# JN5168_Programmer.net
KiCad netlist of a schematic drawn in EAGLE
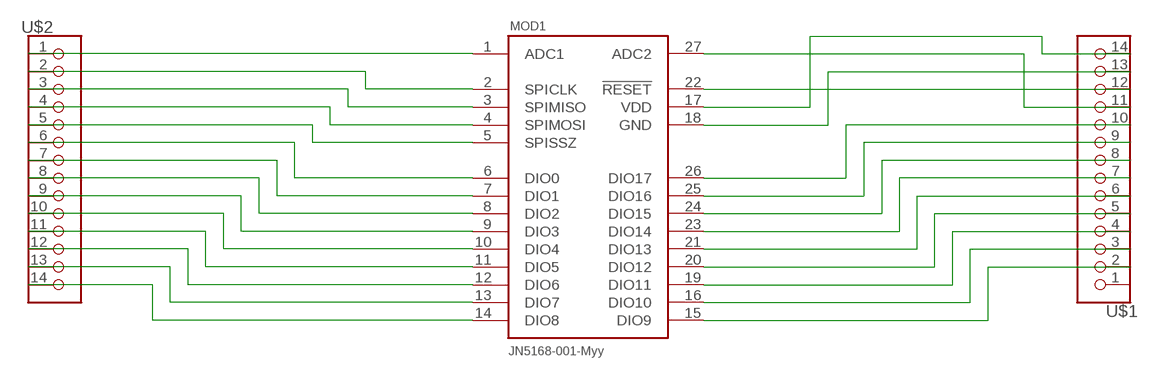
[diagram p0: schematic, sheet 1]

(export (version "E")
  (design (tool "Eeschema 10.0.6"))
  (components
    (comp (ref "MOD1")
      (value "JN5168-001-M00")
      (footprint "eagle-import:JN5168-001-M00")
      (libsource (lib "eagle-import") (part "JN5168-001-M00"))
    )
    (comp (ref "U$1")
      (value "HEADER_1X14_100MIL_PTH")
      (footprint "eagle-import:HEADER_100MIL_1X14_PTH")
      (libsource (lib "eagle-import") (part "HEADER_1X14_100MIL_PTH"))
    )
    (comp (ref "U$2")
      (value "HEADER_1X14_100MIL_PTH")
      (footprint "eagle-import:HEADER_100MIL_1X14_PTH")
      (libsource (lib "eagle-import") (part "HEADER_1X14_100MIL_PTH"))
    )
  )
  (nets
    (net (code "1") (name "Net-(MOD1-ADC1)") (class "Default")
      (node (ref "MOD1") (pin "1") (pinfunction "ADC1_1") (pintype "bidirectional"))
      (node (ref "U$2") (pin "1") (pinfunction "1_1") (pintype "passive"))
    )
    (net (code "2") (name "Net-(MOD1-ADC2)") (class "Default")
      (node (ref "MOD1") (pin "27") (pinfunction "ADC2_27") (pintype "bidirectional"))
      (node (ref "U$1") (pin "11") (pinfunction "11_11") (pintype "passive"))
    )
    (net (code "3") (name "Net-(MOD1-DIO0)") (class "Default")
      (node (ref "MOD1") (pin "6") (pinfunction "DIO0_6") (pintype "bidirectional"))
      (node (ref "U$2") (pin "6") (pinfunction "6_6") (pintype "passive"))
    )
    (net (code "4") (name "Net-(MOD1-DIO1)") (class "Default")
      (node (ref "MOD1") (pin "7") (pinfunction "DIO1_7") (pintype "bidirectional"))
      (node (ref "U$2") (pin "7") (pinfunction "7_7") (pintype "passive"))
    )
    (net (code "5") (name "Net-(MOD1-DIO2)") (class "Default")
      (node (ref "MOD1") (pin "8") (pinfunction "DIO2_8") (pintype "bidirectional"))
      (node (ref "U$2") (pin "8") (pinfunction "8_8") (pintype "passive"))
    )
    (net (code "6") (name "Net-(MOD1-DIO3)") (class "Default")
      (node (ref "MOD1") (pin "9") (pinfunction "DIO3_9") (pintype "bidirectional"))
      (node (ref "U$2") (pin "9") (pinfunction "9_9") (pintype "passive"))
    )
    (net (code "7") (name "Net-(MOD1-DIO4)") (class "Default")
      (node (ref "MOD1") (pin "10") (pinfunction "DIO4_10") (pintype "bidirectional"))
      (node (ref "U$2") (pin "10") (pinfunction "10_10") (pintype "passive"))
    )
    (net (code "8") (name "Net-(MOD1-DIO5)") (class "Default")
      (node (ref "MOD1") (pin "11") (pinfunction "DIO5_11") (pintype "bidirectional"))
      (node (ref "U$2") (pin "11") (pinfunction "11_11") (pintype "passive"))
    )
    (net (code "9") (name "Net-(MOD1-DIO6)") (class "Default")
      (node (ref "MOD1") (pin "12") (pinfunction "DIO6_12") (pintype "bidirectional"))
      (node (ref "U$2") (pin "12") (pinfunction "12_12") (pintype "passive"))
    )
    (net (code "10") (name "Net-(MOD1-DIO7)") (class "Default")
      (node (ref "MOD1") (pin "13") (pinfunction "DIO7_13") (pintype "bidirectional"))
      (node (ref "U$2") (pin "13") (pinfunction "13_13") (pintype "passive"))
    )
    (net (code "11") (name "Net-(MOD1-DIO8)") (class "Default")
      (node (ref "MOD1") (pin "14") (pinfunction "DIO8_14") (pintype "bidirectional"))
      (node (ref "U$2") (pin "14") (pinfunction "14_14") (pintype "passive"))
    )
    (net (code "12") (name "Net-(MOD1-DIO9)") (class "Default")
      (node (ref "MOD1") (pin "15") (pinfunction "DIO9_15") (pintype "bidirectional"))
      (node (ref "U$1") (pin "2") (pinfunction "2_2") (pintype "passive"))
    )
    (net (code "13") (name "Net-(MOD1-DIO10)") (class "Default")
      (node (ref "MOD1") (pin "16") (pinfunction "DIO10_16") (pintype "bidirectional"))
      (node (ref "U$1") (pin "3") (pinfunction "3_3") (pintype "passive"))
    )
    (net (code "14") (name "Net-(MOD1-DIO11)") (class "Default")
      (node (ref "MOD1") (pin "19") (pinfunction "DIO11_19") (pintype "bidirectional"))
      (node (ref "U$1") (pin "4") (pinfunction "4_4") (pintype "passive"))
    )
    (net (code "15") (name "Net-(MOD1-DIO12)") (class "Default")
      (node (ref "MOD1") (pin "20") (pinfunction "DIO12_20") (pintype "bidirectional"))
      (node (ref "U$1") (pin "5") (pinfunction "5_5") (pintype "passive"))
    )
    (net (code "16") (name "Net-(MOD1-DIO13)") (class "Default")
      (node (ref "MOD1") (pin "21") (pinfunction "DIO13_21") (pintype "bidirectional"))
      (node (ref "U$1") (pin "6") (pinfunction "6_6") (pintype "passive"))
    )
    (net (code "17") (name "Net-(MOD1-DIO14)") (class "Default")
      (node (ref "MOD1") (pin "23") (pinfunction "DIO14_23") (pintype "bidirectional"))
      (node (ref "U$1") (pin "7") (pinfunction "7_7") (pintype "passive"))
    )
    (net (code "18") (name "Net-(MOD1-DIO15)") (class "Default")
      (node (ref "MOD1") (pin "24") (pinfunction "DIO15_24") (pintype "bidirectional"))
      (node (ref "U$1") (pin "8") (pinfunction "8_8") (pintype "passive"))
    )
    (net (code "19") (name "Net-(MOD1-DIO16)") (class "Default")
      (node (ref "MOD1") (pin "25") (pinfunction "DIO16_25") (pintype "bidirectional"))
      (node (ref "U$1") (pin "9") (pinfunction "9_9") (pintype "passive"))
    )
    (net (code "20") (name "Net-(MOD1-DIO17)") (class "Default")
      (node (ref "MOD1") (pin "26") (pinfunction "DIO17_26") (pintype "bidirectional"))
      (node (ref "U$1") (pin "10") (pinfunction "10_10") (pintype "passive"))
    )
    (net (code "21") (name "Net-(MOD1-GND)") (class "Default")
      (node (ref "MOD1") (pin "18") (pinfunction "GND_18") (pintype "power_in"))
      (node (ref "U$1") (pin "13") (pinfunction "13_13") (pintype "passive"))
    )
    (net (code "22") (name "Net-(MOD1-SPICLK)") (class "Default")
      (node (ref "MOD1") (pin "2") (pinfunction "SPICLK_2") (pintype "bidirectional"))
      (node (ref "U$2") (pin "2") (pinfunction "2_2") (pintype "passive"))
    )
    (net (code "23") (name "Net-(MOD1-SPIMISO)") (class "Default")
      (node (ref "MOD1") (pin "3") (pinfunction "SPIMISO_3") (pintype "bidirectional"))
      (node (ref "U$2") (pin "3") (pinfunction "3_3") (pintype "passive"))
    )
    (net (code "24") (name "Net-(MOD1-SPIMOSI)") (class "Default")
      (node (ref "MOD1") (pin "4") (pinfunction "SPIMOSI_4") (pintype "bidirectional"))
      (node (ref "U$2") (pin "4") (pinfunction "4_4") (pintype "passive"))
    )
    (net (code "25") (name "Net-(MOD1-SPISSZ)") (class "Default")
      (node (ref "MOD1") (pin "5") (pinfunction "SPISSZ_5") (pintype "bidirectional"))
      (node (ref "U$2") (pin "5") (pinfunction "5_5") (pintype "passive"))
    )
    (net (code "26") (name "Net-(MOD1-VDD)") (class "Default")
      (node (ref "MOD1") (pin "17") (pinfunction "VDD_17") (pintype "power_in"))
      (node (ref "U$1") (pin "14") (pinfunction "14_14") (pintype "passive"))
    )
    (net (code "27") (name "Net-(MOD1-~{RESET})") (class "Default")
      (node (ref "MOD1") (pin "22") (pinfunction "~{RESET}_22") (pintype "input"))
      (node (ref "U$1") (pin "12") (pinfunction "12_12") (pintype "passive"))
    )
    (net (code "28") (name "unconnected-(U$1-Pad1)") (class "Default")
      (node (ref "U$1") (pin "1") (pinfunction "1_1") (pintype "passive"))
    )
  )
)
